# IMU.net
KiCad netlist of a schematic drawn in Altium Designer
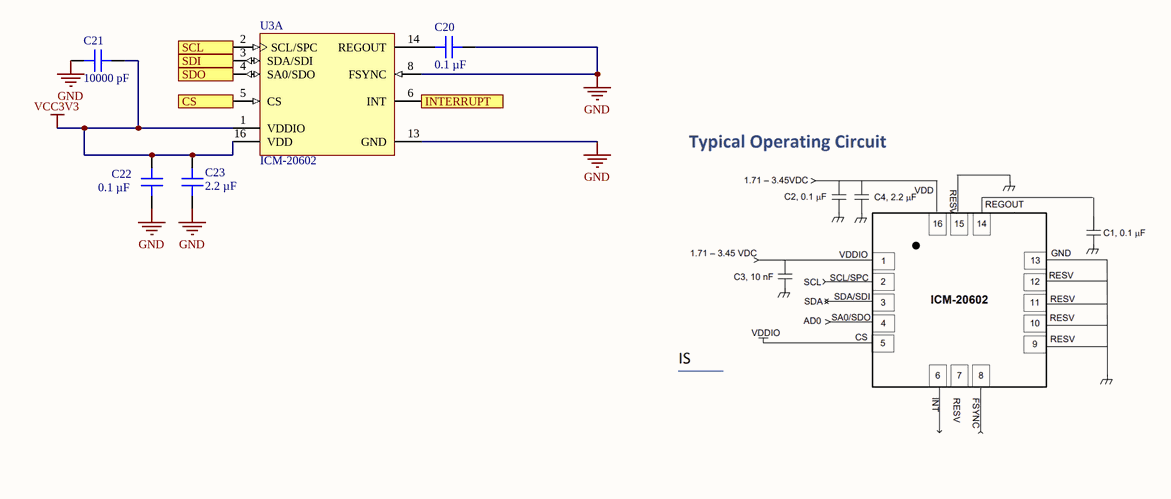
[diagram p0: IMU.SchDoc]

(export (version "E")
  (design (tool "Eeschema 10.0.6"))
  (components
    (comp (ref "C20")
      (value "0.1 µF")
      (footprint "CAP 0603_1608")
      (description "CAP CER 0.1UF 50V X7R 0603")
      (fields (field (name "PART NUMBER") "C0603C104K5RAC7411") (field (name "MANUFACTURER") "KEMET"))
      (libsource (lib "Celestial Altium Library - altium_library") (part "Capacitor"))
    )
    (comp (ref "C21")
      (value "10000 pF")
      (footprint "CAP 0603_1608")
      (description "CAP CER 0603 10NF 16V X7R 10%")
      (fields (field (name "PART NUMBER") "C0603C103K4RECAUTO") (field (name "MANUFACTURER") "KEMET"))
      (libsource (lib "Celestial Altium Library - altium_library") (part "Capacitor"))
    )
    (comp (ref "C22")
      (value "0.1 µF")
      (footprint "CAP 0603_1608")
      (description "CAP CER 0.1UF 50V X7R 0603")
      (fields (field (name "PART NUMBER") "C0603C104K5RAC7411") (field (name "MANUFACTURER") "KEMET"))
      (libsource (lib "Celestial Altium Library - altium_library") (part "Capacitor"))
    )
    (comp (ref "C23")
      (value "2.2 µF")
      (footprint "CAP 0603_1608")
      (description "CAP CER 2.2UF 10V Y5V 0603")
      (fields (field (name "PART NUMBER") "CC0603ZRY5V6BB225") (field (name "MANUFACTURER") "Yageo"))
      (libsource (lib "Celestial Altium Library - altium_library") (part "Capacitor"))
    )
    (comp (ref "U3")
      (value "ICM-20602")
      (footprint "INSE-I62-16")
      (fields (field (name "MANUFACTURER") "InvenSense"))
      (libsource (lib "Altium Content Vault") (part "INSE-ICM-20602-16"))
    )
  )
  (nets
    (net (code "1") (name "/CS") (class "Default")
      (node (ref "U3") (pin "5") (pinfunction "CS_5") (pintype "input"))
    )
    (net (code "2") (name "/INTERRUPT") (class "Default")
      (node (ref "U3") (pin "6") (pinfunction "INT_6") (pintype "open_collector"))
    )
    (net (code "3") (name "/SCL") (class "Default")
      (node (ref "U3") (pin "2") (pinfunction "SCL/SPC_2") (pintype "input"))
    )
    (net (code "4") (name "/SDI") (class "Default")
      (node (ref "U3") (pin "3") (pinfunction "SDA/SDI_3") (pintype "bidirectional"))
    )
    (net (code "5") (name "/SDO") (class "Default")
      (node (ref "U3") (pin "4") (pinfunction "SA0/SDO_4") (pintype "bidirectional"))
    )
    (net (code "6") (name "GND") (class "Default")
      (node (ref "C20") (pin "2") (pinfunction "2_2") (pintype "passive"))
      (node (ref "C21") (pin "1") (pinfunction "1_1") (pintype "passive"))
      (node (ref "C22") (pin "1") (pinfunction "1_1") (pintype "passive"))
      (node (ref "C23") (pin "1") (pinfunction "1_1") (pintype "passive"))
      (node (ref "U3") (pin "13") (pinfunction "GND_13") (pintype "power_in"))
      (node (ref "U3") (pin "8") (pinfunction "FSYNC_8") (pintype "input"))
    )
    (net (code "7") (name "Net-(U3A-REGOUT)") (class "Default")
      (node (ref "C20") (pin "1") (pinfunction "1_1") (pintype "passive"))
      (node (ref "U3") (pin "14") (pinfunction "REGOUT_14") (pintype "passive"))
    )
    (net (code "8") (name "VCC3V3") (class "Default")
      (node (ref "C21") (pin "2") (pinfunction "2_2") (pintype "passive"))
      (node (ref "C22") (pin "2") (pinfunction "2_2") (pintype "passive"))
      (node (ref "C23") (pin "2") (pinfunction "2_2") (pintype "passive"))
      (node (ref "U3") (pin "1") (pinfunction "VDDIO_1") (pintype "power_in"))
      (node (ref "U3") (pin "16") (pinfunction "VDD_16") (pintype "power_in"))
    )
  )
)
